# SparkFun_GPS_ZED-F9R_BoB.net
KiCad netlist of a schematic drawn in EAGLE
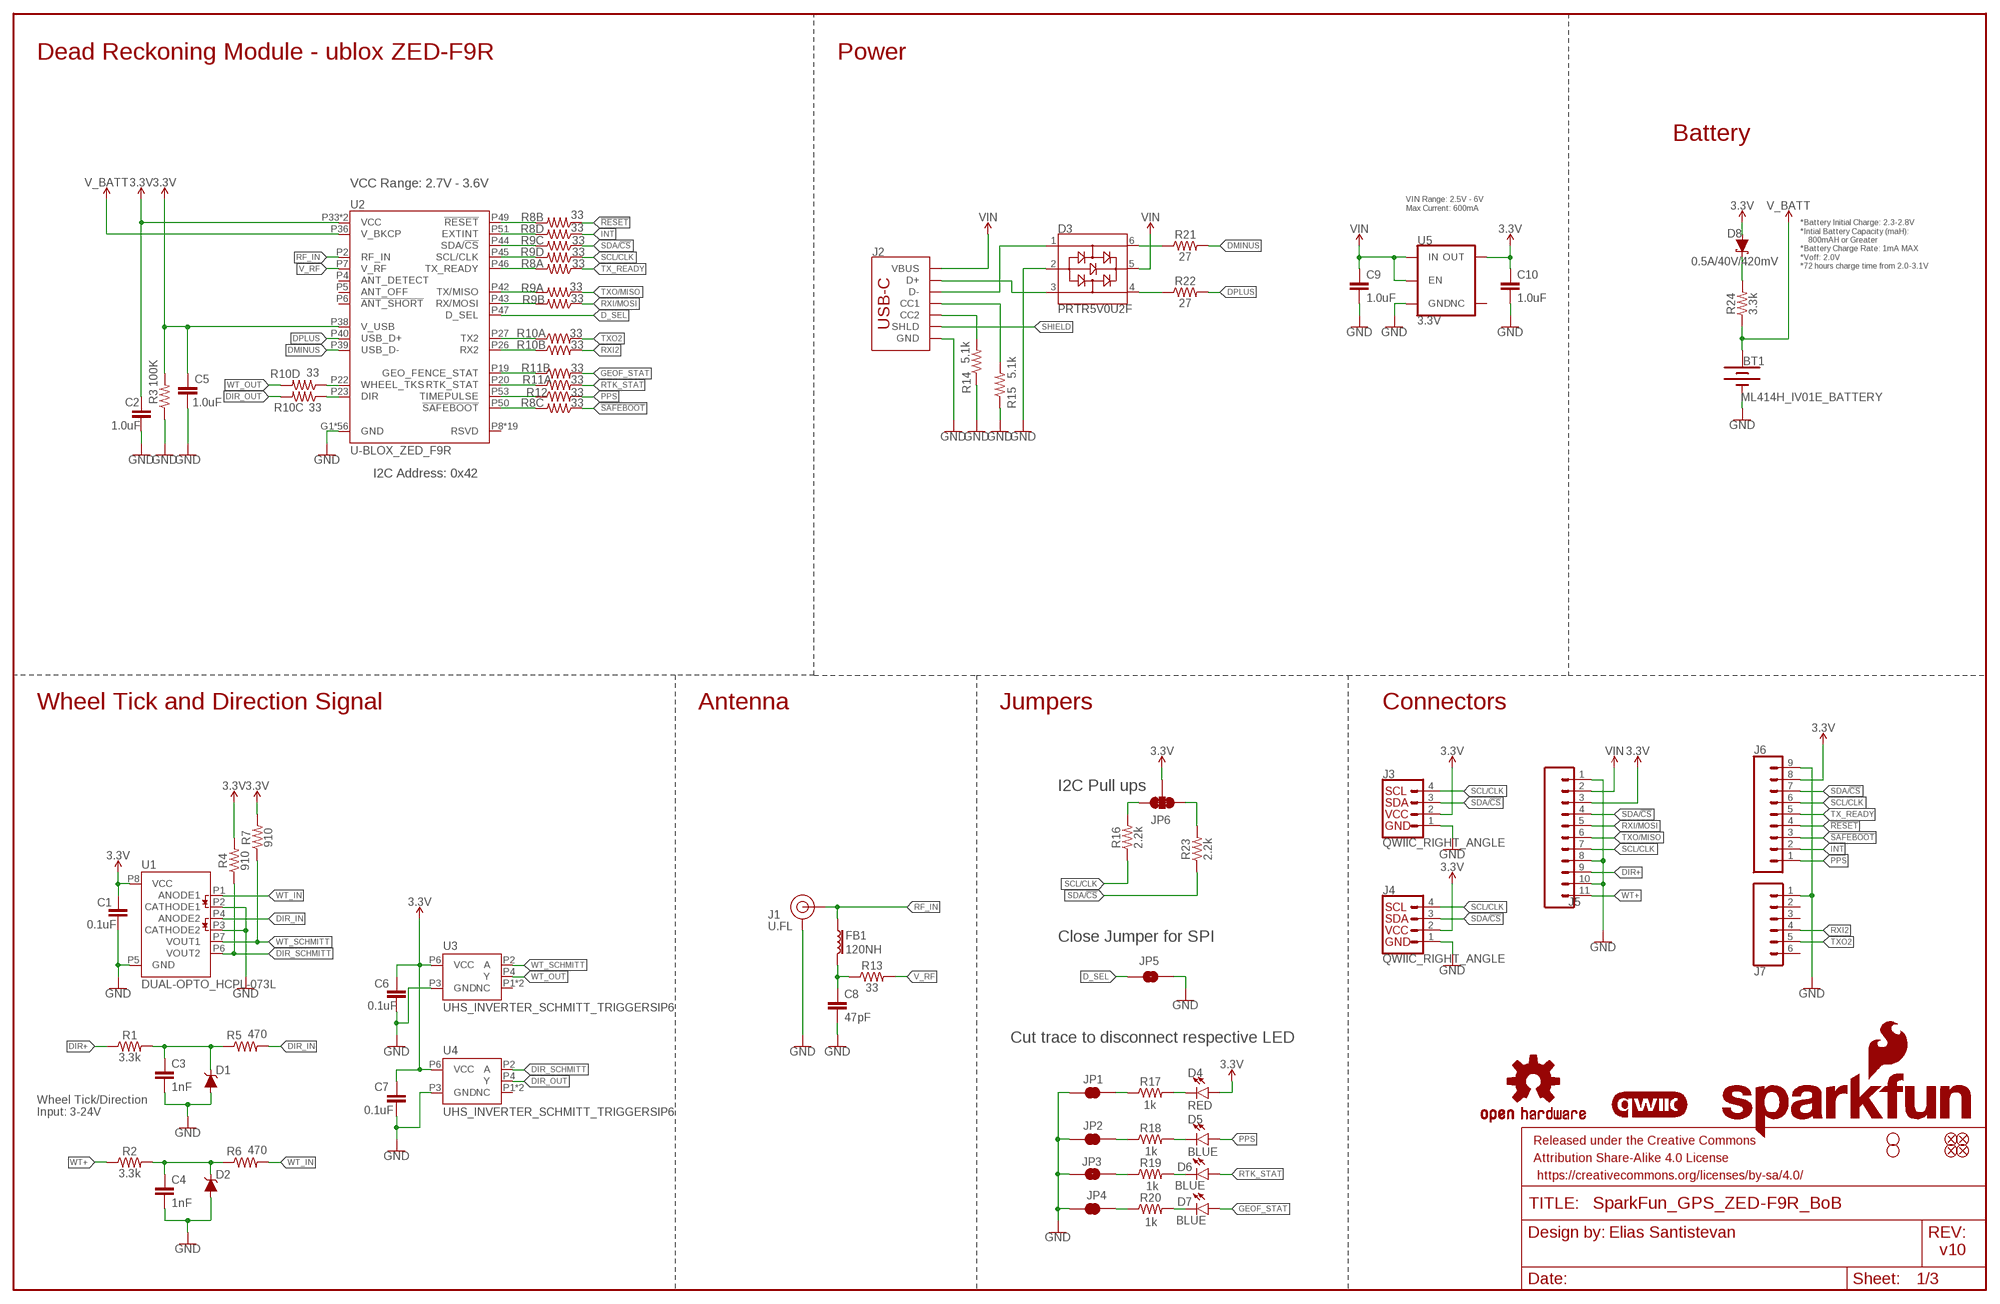
[diagram p0: schematic, sheet 1]

(export (version "E")
  (design (tool "Eeschema 10.0.6"))
  (components
    (comp (ref "$1_25_$_2020-03-30_22-52-05")
      (value "STAND-OFFTIGHT")
      (footprint "eagle-import:STAND-OFF-TIGHT")
      (libsource (lib "eagle-import") (part "STAND-OFFTIGHT"))
    )
    (comp (ref "BT1")
      (value "ML414H_IV01E_BATTERY")
      (footprint "eagle-import:ML414H_IV01E")
      (libsource (lib "eagle-import") (part "ML414H_IV01E_BATTERY"))
    )
    (comp (ref "C1")
      (value "0.1uF")
      (footprint "eagle-import:0402")
      (libsource (lib "eagle-import") (part "0.1UF-0402-10V-10%-X7R"))
    )
    (comp (ref "C2")
      (value "1.0uF")
      (footprint "eagle-import:0603")
      (libsource (lib "eagle-import") (part "1.0UF-0603-16V-10%-X7R"))
    )
    (comp (ref "C3")
      (value "1nF")
      (footprint "eagle-import:0402")
      (libsource (lib "eagle-import") (part "1.0NF/1000PF-0402-25V-10%-X7R"))
    )
    (comp (ref "C4")
      (value "1nF")
      (footprint "eagle-import:0402")
      (libsource (lib "eagle-import") (part "1.0NF/1000PF-0402-25V-10%-X7R"))
    )
    (comp (ref "C5")
      (value "1.0uF")
      (footprint "eagle-import:0603")
      (libsource (lib "eagle-import") (part "1.0UF-0603-16V-10%-X7R"))
    )
    (comp (ref "C6")
      (value "0.1uF")
      (footprint "eagle-import:0402")
      (libsource (lib "eagle-import") (part "0.1UF-0402-10V-10%-X7R"))
    )
    (comp (ref "C7")
      (value "0.1uF")
      (footprint "eagle-import:0402")
      (libsource (lib "eagle-import") (part "0.1UF-0402-10V-10%-X7R"))
    )
    (comp (ref "C8")
      (value "47pF")
      (footprint "eagle-import:0402")
      (libsource (lib "eagle-import") (part "47PF-0402-25V-5%-X7R"))
    )
    (comp (ref "C9")
      (value "1.0uF")
      (footprint "eagle-import:0603")
      (libsource (lib "eagle-import") (part "1.0UF-0603-16V-10%-X7R"))
    )
    (comp (ref "C10")
      (value "1.0uF")
      (footprint "eagle-import:0603")
      (libsource (lib "eagle-import") (part "1.0UF-0603-16V-10%-X7R"))
    )
    (comp (ref "D1")
      (value "15V")
      (footprint "eagle-import:SOT23-3")
      (libsource (lib "eagle-import") (part "DIODE-ZENER-BZX84C15LT3G"))
    )
    (comp (ref "D2")
      (value "15V")
      (footprint "eagle-import:SOT23-3")
      (libsource (lib "eagle-import") (part "DIODE-ZENER-BZX84C15LT3G"))
    )
    (comp (ref "D3")
      (value "PRTR5V0U2F")
      (footprint "eagle-import:SOT886")
      (libsource (lib "eagle-import") (part "PRTR5V0U2F"))
    )
    (comp (ref "D4")
      (value "RED")
      (footprint "eagle-import:LED-0603")
      (libsource (lib "eagle-import") (part "LED-RED0603"))
    )
    (comp (ref "D5")
      (value "BLUE")
      (footprint "eagle-import:LED-0603")
      (libsource (lib "eagle-import") (part "LED-BLUE0603"))
    )
    (comp (ref "D6")
      (value "BLUE")
      (footprint "eagle-import:LED-0603")
      (libsource (lib "eagle-import") (part "LED-BLUE0603"))
    )
    (comp (ref "D7")
      (value "BLUE")
      (footprint "eagle-import:LED-0603")
      (libsource (lib "eagle-import") (part "LED-BLUE0603"))
    )
    (comp (ref "D8")
      (value "0.5A/40V/420mV")
      (footprint "eagle-import:SOD-323")
      (libsource (lib "eagle-import") (part "DIODE-SCHOTTKY-PMEG4005EJ"))
    )
    (comp (ref "FB1")
      (value "120NH")
      (footprint "eagle-import:0402_MURATA")
      (libsource (lib "eagle-import") (part "FERRITE_BEAD_GNSS"))
    )
    (comp (ref "FD1")
      (value "FIDUCIALUFIDUCIAL")
      (footprint "eagle-import:FIDUCIAL-MICRO")
      (libsource (lib "eagle-import") (part "FIDUCIALUFIDUCIAL"))
    )
    (comp (ref "FD2")
      (value "FIDUCIALUFIDUCIAL")
      (footprint "eagle-import:FIDUCIAL-MICRO")
      (libsource (lib "eagle-import") (part "FIDUCIALUFIDUCIAL"))
    )
    (comp (ref "FD3")
      (value "FIDUCIALUFIDUCIAL")
      (footprint "eagle-import:FIDUCIAL-MICRO")
      (libsource (lib "eagle-import") (part "FIDUCIALUFIDUCIAL"))
    )
    (comp (ref "FD4")
      (value "FIDUCIALUFIDUCIAL")
      (footprint "eagle-import:FIDUCIAL-MICRO")
      (libsource (lib "eagle-import") (part "FIDUCIALUFIDUCIAL"))
    )
    (comp (ref "FRAME1")
      (value "FRAME-LEDGER")
      (footprint "eagle-import:CREATIVE_COMMONS")
      (libsource (lib "eagle-import") (part "FRAME-LEDGER"))
    )
    (comp (ref "H2")
      (value "STAND-OFFTIGHT")
      (footprint "eagle-import:STAND-OFF-TIGHT")
      (libsource (lib "eagle-import") (part "STAND-OFFTIGHT"))
    )
    (comp (ref "J1")
      (value "U.FL")
      (footprint "eagle-import:U.FL")
      (libsource (lib "eagle-import") (part "U.FL2PIN"))
    )
    (comp (ref "J2")
      (value "USB_C_2-LAYER_PADS")
      (footprint "eagle-import:USB-C-16P-2LAYER-PADS")
      (libsource (lib "eagle-import") (part "USB_C_2-LAYER_PADS"))
    )
    (comp (ref "J3")
      (value "QWIIC_RIGHT_ANGLE")
      (footprint "eagle-import:JST04_1MM_RA")
      (libsource (lib "eagle-import") (part "QWIIC_CONNECTORJS-1MM"))
    )
    (comp (ref "J4")
      (value "QWIIC_RIGHT_ANGLE")
      (footprint "eagle-import:JST04_1MM_RA")
      (libsource (lib "eagle-import") (part "QWIIC_CONNECTORJS-1MM"))
    )
    (comp (ref "J5")
      (value "CONN_111X11_NO_SILK")
      (footprint "eagle-import:1X11_NO_SILK")
      (libsource (lib "eagle-import") (part "CONN_111X11_NO_SILK"))
    )
    (comp (ref "J6")
      (value "CONN_09NO_SILK")
      (footprint "eagle-import:1X09_NO_SILK")
      (libsource (lib "eagle-import") (part "CONN_09NO_SILK"))
    )
    (comp (ref "J7")
      (value "CONN_06NO_SILK_NO_POP")
      (footprint "eagle-import:1X06_NO_SILK")
      (libsource (lib "eagle-import") (part "CONN_06NO_SILK_NO_POP"))
    )
    (comp (ref "JP1")
      (value "JUMPER-SMT_2_NC_TRACE_SILK")
      (footprint "eagle-import:SMT-JUMPER_2_NC_TRACE_SILK")
      (libsource (lib "eagle-import") (part "JUMPER-SMT_2_NC_TRACE_SILK"))
    )
    (comp (ref "JP2")
      (value "JUMPER-SMT_2_NC_TRACE_SILK")
      (footprint "eagle-import:SMT-JUMPER_2_NC_TRACE_SILK")
      (libsource (lib "eagle-import") (part "JUMPER-SMT_2_NC_TRACE_SILK"))
    )
    (comp (ref "JP3")
      (value "JUMPER-SMT_2_NC_TRACE_SILK")
      (footprint "eagle-import:SMT-JUMPER_2_NC_TRACE_SILK")
      (libsource (lib "eagle-import") (part "JUMPER-SMT_2_NC_TRACE_SILK"))
    )
    (comp (ref "JP4")
      (value "JUMPER-SMT_2_NC_TRACE_SILK")
      (footprint "eagle-import:SMT-JUMPER_2_NC_TRACE_SILK")
      (libsource (lib "eagle-import") (part "JUMPER-SMT_2_NC_TRACE_SILK"))
    )
    (comp (ref "JP5")
      (value "JUMPER-SMT_2_NO_SILK")
      (footprint "eagle-import:SMT-JUMPER_2_NO_SILK")
      (libsource (lib "eagle-import") (part "JUMPER-SMT_2_NO_SILK"))
    )
    (comp (ref "JP6")
      (value "JUMPER-SMT_3_2-NC_TRACE_SILK")
      (footprint "eagle-import:SMT-JUMPER_3_2-NC_TRACE_SILK")
      (libsource (lib "eagle-import") (part "JUMPER-SMT_3_2-NC_TRACE_SILK"))
    )
    (comp (ref "LOGO1")
      (value "OSHW-LOGOM")
      (footprint "eagle-import:OSHW-LOGO-M")
      (libsource (lib "eagle-import") (part "OSHW-LOGOM"))
    )
    (comp (ref "LOGO2")
      (value "QWIIC_LOGO_4MM")
      (footprint "eagle-import:QWIIC_4MM")
      (libsource (lib "eagle-import") (part "QWIIC_LOGO_4MM"))
    )
    (comp (ref "LOGO3")
      (value "SFE_LOGO_NAME_FLAME.2_INCH")
      (footprint "eagle-import:SFE_LOGO_NAME_FLAME_.2")
      (libsource (lib "eagle-import") (part "SFE_LOGO_NAME_FLAME.2_INCH"))
    )
    (comp (ref "R1")
      (value "3.3k")
      (footprint "eagle-import:0603")
      (libsource (lib "eagle-import") (part "3.3KOHM-0603-1/10W-1%"))
    )
    (comp (ref "R2")
      (value "3.3k")
      (footprint "eagle-import:0603")
      (libsource (lib "eagle-import") (part "3.3KOHM-0603-1/10W-1%"))
    )
    (comp (ref "R3")
      (value "100K")
      (footprint "eagle-import:0402")
      (libsource (lib "eagle-import") (part "100KOHM-0402-1/16W-1%"))
    )
    (comp (ref "R4")
      (value "910")
      (footprint "eagle-import:0603")
      (libsource (lib "eagle-import") (part "910OHM-0603-1/10W-5%"))
    )
    (comp (ref "R5")
      (value "470")
      (footprint "eagle-import:0603")
      (libsource (lib "eagle-import") (part "470OHM-0603-1/10W-1%"))
    )
    (comp (ref "R6")
      (value "470")
      (footprint "eagle-import:0603")
      (libsource (lib "eagle-import") (part "470OHM-0603-1/10W-1%"))
    )
    (comp (ref "R7")
      (value "910")
      (footprint "eagle-import:0603")
      (libsource (lib "eagle-import") (part "910OHM-0603-1/10W-5%"))
    )
    (comp (ref "R8")
      (value "33")
      (footprint "eagle-import:1206_RA")
      (libsource (lib "eagle-import") (part "33OHM_RA-1206-1/16W-5%"))
    )
    (comp (ref "R9")
      (value "33")
      (footprint "eagle-import:1206_RA")
      (libsource (lib "eagle-import") (part "33OHM_RA-1206-1/16W-5%"))
    )
    (comp (ref "R10")
      (value "33")
      (footprint "eagle-import:1206_RA")
      (libsource (lib "eagle-import") (part "33OHM_RA-1206-1/16W-5%"))
    )
    (comp (ref "R11")
      (value "33")
      (footprint "eagle-import:1206_RA")
      (libsource (lib "eagle-import") (part "33OHM_RA-1206-1/16W-5%"))
    )
    (comp (ref "R12")
      (value "33")
      (footprint "eagle-import:0603")
      (libsource (lib "eagle-import") (part "33OHM-0603-1/10W-1%"))
    )
    (comp (ref "R13")
      (value "33")
      (footprint "eagle-import:0603")
      (libsource (lib "eagle-import") (part "33OHM-0603-1/10W-1%"))
    )
    (comp (ref "R14")
      (value "5.1k")
      (footprint "eagle-import:0402")
      (libsource (lib "eagle-import") (part "5.1KOHM-0402-1/16W-1%"))
    )
    (comp (ref "R15")
      (value "5.1k")
      (footprint "eagle-import:0402")
      (libsource (lib "eagle-import") (part "5.1KOHM-0402-1/16W-1%"))
    )
    (comp (ref "R16")
      (value "2.2k")
      (footprint "eagle-import:0603")
      (libsource (lib "eagle-import") (part "2.2KOHM-0603-1/10W-1%"))
    )
    (comp (ref "R17")
      (value "1KOHM-0402-1/16W-1%")
      (footprint "eagle-import:0402")
      (libsource (lib "eagle-import") (part "1KOHM-0402-1/16W-1%"))
    )
    (comp (ref "R18")
      (value "1KOHM-0402-1/16W-1%")
      (footprint "eagle-import:0402")
      (libsource (lib "eagle-import") (part "1KOHM-0402-1/16W-1%"))
    )
    (comp (ref "R19")
      (value "1KOHM-0402-1/16W-1%")
      (footprint "eagle-import:0402")
      (libsource (lib "eagle-import") (part "1KOHM-0402-1/16W-1%"))
    )
    (comp (ref "R20")
      (value "1KOHM-0402-1/16W-1%")
      (footprint "eagle-import:0402")
      (libsource (lib "eagle-import") (part "1KOHM-0402-1/16W-1%"))
    )
    (comp (ref "R21")
      (value "27")
      (footprint "eagle-import:0603")
      (libsource (lib "eagle-import") (part "27OHM-0603-1/10W-1%"))
    )
    (comp (ref "R22")
      (value "27")
      (footprint "eagle-import:0603")
      (libsource (lib "eagle-import") (part "27OHM-0603-1/10W-1%"))
    )
    (comp (ref "R23")
      (value "2.2k")
      (footprint "eagle-import:0603")
      (libsource (lib "eagle-import") (part "2.2KOHM-0603-1/10W-1%"))
    )
    (comp (ref "R24")
      (value "3.3k")
      (footprint "eagle-import:0603")
      (libsource (lib "eagle-import") (part "3.3KOHM-0603-1/10W-1%"))
    )
    (comp (ref "U1")
      (value "DUAL-OPTO_HCPL-073L")
      (footprint "eagle-import:SOP_8-PIN")
      (libsource (lib "eagle-import") (part "DUAL-OPTO_HCPL-073L"))
    )
    (comp (ref "U2")
      (value "U-BLOX_ZED_F9R")
      (footprint "eagle-import:UBLOX_ZED_F9R")
      (libsource (lib "eagle-import") (part "U-BLOX_ZED_F9R"))
    )
    (comp (ref "U3")
      (value "UHS_INVERTER_SCHMITT_TRIGGERSIP6")
      (footprint "eagle-import:SIP6")
      (libsource (lib "eagle-import") (part "UHS_INVERTER_SCHMITT_TRIGGERSIP6"))
    )
    (comp (ref "U4")
      (value "UHS_INVERTER_SCHMITT_TRIGGERSIP6")
      (footprint "eagle-import:SIP6")
      (libsource (lib "eagle-import") (part "UHS_INVERTER_SCHMITT_TRIGGERSIP6"))
    )
    (comp (ref "U5")
      (value "3.3V")
      (footprint "eagle-import:SOT23-5")
      (libsource (lib "eagle-import") (part "V_REG_AP2112K-3.3V"))
    )
  )
  (nets
    (net (code "1") (name "3.3V") (class "Default")
      (node (ref "C1") (pin "1") (pinfunction "1_1") (pintype "passive"))
      (node (ref "C10") (pin "1") (pinfunction "1_1") (pintype "passive"))
      (node (ref "C2") (pin "1") (pinfunction "1_1") (pintype "passive"))
      (node (ref "C5") (pin "1") (pinfunction "1_1") (pintype "passive"))
      (node (ref "C6") (pin "1") (pinfunction "1_1") (pintype "passive"))
      (node (ref "C7") (pin "1") (pinfunction "1_1") (pintype "passive"))
      (node (ref "D4") (pin "A") (pinfunction "A_A") (pintype "passive"))
      (node (ref "D8") (pin "A") (pinfunction "A_A") (pintype "passive"))
      (node (ref "J3") (pin "2") (pinfunction "2_2") (pintype "power_in"))
      (node (ref "J4") (pin "2") (pinfunction "2_2") (pintype "power_in"))
      (node (ref "J5") (pin "3") (pinfunction "3_3") (pintype "passive"))
      (node (ref "J6") (pin "8") (pinfunction "8_8") (pintype "passive"))
      (node (ref "JP6") (pin "2") (pinfunction "2_2") (pintype "passive"))
      (node (ref "R3") (pin "2") (pinfunction "2_2") (pintype "passive"))
      (node (ref "R4") (pin "2") (pinfunction "2_2") (pintype "passive"))
      (node (ref "R7") (pin "2") (pinfunction "2_2") (pintype "passive"))
      (node (ref "U1") (pin "P8") (pinfunction "VCC_P8") (pintype "power_in"))
      (node (ref "U2") (pin "P33") (pinfunction "VCC_P33") (pintype "power_in"))
      (node (ref "U2") (pin "P34") (pinfunction "VCC_P34") (pintype "power_in"))
      (node (ref "U2") (pin "P38") (pinfunction "V_USB_P38") (pintype "power_in"))
      (node (ref "U3") (pin "P6") (pinfunction "VCC_P6") (pintype "power_in"))
      (node (ref "U4") (pin "P6") (pinfunction "VCC_P6") (pintype "power_in"))
      (node (ref "U5") (pin "5") (pinfunction "OUT_5") (pintype "passive"))
    )
    (net (code "2") (name "DIR+") (class "Default")
      (node (ref "J5") (pin "9") (pinfunction "9_9") (pintype "passive"))
      (node (ref "R1") (pin "1") (pinfunction "1_1") (pintype "passive"))
    )
    (net (code "3") (name "DIR_IN") (class "Default")
      (node (ref "R5") (pin "2") (pinfunction "2_2") (pintype "passive"))
      (node (ref "U1") (pin "P4") (pinfunction "ANODE2_P4") (pintype "input"))
    )
    (net (code "4") (name "DIR_OUT") (class "Default")
      (node (ref "R10") (pin "P6") (pinfunction "2_P6") (pintype "passive"))
      (node (ref "U4") (pin "P4") (pinfunction "Y_P4") (pintype "bidirectional"))
    )
    (net (code "5") (name "DIR_SCHMITT") (class "Default")
      (node (ref "R4") (pin "1") (pinfunction "1_1") (pintype "passive"))
      (node (ref "U1") (pin "P6") (pinfunction "VOUT2_P6") (pintype "output"))
      (node (ref "U4") (pin "P2") (pinfunction "A_P2") (pintype "bidirectional"))
    )
    (net (code "6") (name "DMINUS") (class "Default")
      (node (ref "R21") (pin "2") (pinfunction "2_2") (pintype "passive"))
      (node (ref "U2") (pin "P39") (pinfunction "USB_D-_P39") (pintype "bidirectional"))
    )
    (net (code "7") (name "DPLUS") (class "Default")
      (node (ref "R22") (pin "2") (pinfunction "2_2") (pintype "passive"))
      (node (ref "U2") (pin "P40") (pinfunction "USB_D+_P40") (pintype "bidirectional"))
    )
    (net (code "8") (name "D_SEL") (class "Default")
      (node (ref "JP5") (pin "1") (pinfunction "1_1") (pintype "passive"))
      (node (ref "U2") (pin "P47") (pinfunction "D_SEL_P47") (pintype "bidirectional"))
    )
    (net (code "9") (name "GEOF_STAT") (class "Default")
      (node (ref "D7") (pin "A") (pinfunction "A_A") (pintype "passive"))
      (node (ref "R11") (pin "P7") (pinfunction "2_P7") (pintype "passive"))
    )
    (net (code "10") (name "GND") (class "Default")
      (node (ref "BT1") (pin "-") (pinfunction "-_-") (pintype "power_in"))
      (node (ref "C1") (pin "2") (pinfunction "2_2") (pintype "passive"))
      (node (ref "C10") (pin "2") (pinfunction "2_2") (pintype "passive"))
      (node (ref "C2") (pin "2") (pinfunction "2_2") (pintype "passive"))
      (node (ref "C3") (pin "2") (pinfunction "2_2") (pintype "passive"))
      (node (ref "C4") (pin "2") (pinfunction "2_2") (pintype "passive"))
      (node (ref "C5") (pin "2") (pinfunction "2_2") (pintype "passive"))
      (node (ref "C6") (pin "2") (pinfunction "2_2") (pintype "passive"))
      (node (ref "C7") (pin "2") (pinfunction "2_2") (pintype "passive"))
      (node (ref "C8") (pin "2") (pinfunction "2_2") (pintype "passive"))
      (node (ref "C9") (pin "2") (pinfunction "2_2") (pintype "passive"))
      (node (ref "D1") (pin "1") (pinfunction "A_1") (pintype "passive"))
      (node (ref "D2") (pin "1") (pinfunction "A_1") (pintype "passive"))
      (node (ref "D3") (pin "2") (pinfunction "2_2") (pintype "bidirectional"))
      (node (ref "J1") (pin "1") (pinfunction "GND_1") (pintype "bidirectional"))
      (node (ref "J1") (pin "2") (pinfunction "GND_2") (pintype "bidirectional"))
      (node (ref "J2") (pin "GND") (pinfunction "GND_GND") (pintype "bidirectional"))
      (node (ref "J2") (pin "GND2") (pinfunction "GND_GND2") (pintype "bidirectional"))
      (node (ref "J3") (pin "1") (pinfunction "1_1") (pintype "power_in"))
      (node (ref "J4") (pin "1") (pinfunction "1_1") (pintype "power_in"))
      (node (ref "J5") (pin "1") (pinfunction "1_1") (pintype "passive"))
      (node (ref "J5") (pin "10") (pinfunction "10_10") (pintype "passive"))
      (node (ref "J5") (pin "8") (pinfunction "8_8") (pintype "passive"))
      (node (ref "J6") (pin "9") (pinfunction "9_9") (pintype "passive"))
      (node (ref "J7") (pin "1") (pinfunction "1_1") (pintype "passive"))
      (node (ref "JP1") (pin "1") (pinfunction "1_1") (pintype "passive"))
      (node (ref "JP2") (pin "1") (pinfunction "1_1") (pintype "passive"))
      (node (ref "JP3") (pin "1") (pinfunction "1_1") (pintype "passive"))
      (node (ref "JP4") (pin "1") (pinfunction "1_1") (pintype "passive"))
      (node (ref "JP5") (pin "2") (pinfunction "2_2") (pintype "passive"))
      (node (ref "R14") (pin "1") (pinfunction "1_1") (pintype "passive"))
      (node (ref "R15") (pin "1") (pinfunction "1_1") (pintype "passive"))
      (node (ref "R3") (pin "1") (pinfunction "1_1") (pintype "passive"))
      (node (ref "U1") (pin "P2") (pinfunction "CATHODE1_P2") (pintype "input"))
      (node (ref "U1") (pin "P3") (pinfunction "CATHODE2_P3") (pintype "input"))
      (node (ref "U1") (pin "P5") (pinfunction "GND_P5") (pintype "power_in"))
      (node (ref "U2") (pin "G1") (pinfunction "GND_G1") (pintype "power_in"))
      (node (ref "U2") (pin "G10") (pinfunction "GND_G10") (pintype "power_in"))
      (node (ref "U2") (pin "G11") (pinfunction "GND_G11") (pintype "power_in"))
      (node (ref "U2") (pin "G12") (pinfunction "GND_G12") (pintype "power_in"))
      (node (ref "U2") (pin "G13") (pinfunction "GND_G13") (pintype "power_in"))
      (node (ref "U2") (pin "G14") (pinfunction "GND_G14") (pintype "power_in"))
      (node (ref "U2") (pin "G15") (pinfunction "GND_G15") (pintype "power_in"))
      (node (ref "U2") (pin "G16") (pinfunction "GND_G16") (pintype "power_in"))
      (node (ref "U2") (pin "G17") (pinfunction "GND_G17") (pintype "power_in"))
      (node (ref "U2") (pin "G18") (pinfunction "GND_G18") (pintype "power_in"))
      (node (ref "U2") (pin "G19") (pinfunction "GND_G19") (pintype "power_in"))
      (node (ref "U2") (pin "G2") (pinfunction "GND_G2") (pintype "power_in"))
      (node (ref "U2") (pin "G20") (pinfunction "GND_G20") (pintype "power_in"))
      (node (ref "U2") (pin "G21") (pinfunction "GND_G21") (pintype "power_in"))
      (node (ref "U2") (pin "G22") (pinfunction "GND_G22") (pintype "power_in"))
      (node (ref "U2") (pin "G23") (pinfunction "GND_G23") (pintype "power_in"))
      (node (ref "U2") (pin "G24") (pinfunction "GND_G24") (pintype "power_in"))
      (node (ref "U2") (pin "G25") (pinfunction "GND_G25") (pintype "power_in"))
      (node (ref "U2") (pin "G26") (pinfunction "GND_G26") (pintype "power_in"))
      (node (ref "U2") (pin "G27") (pinfunction "GND_G27") (pintype "power_in"))
      (node (ref "U2") (pin "G28") (pinfunction "GND_G28") (pintype "power_in"))
      (node (ref "U2") (pin "G29") (pinfunction "GND_G29") (pintype "power_in"))
      (node (ref "U2") (pin "G3") (pinfunction "GND_G3") (pintype "power_in"))
      (node (ref "U2") (pin "G30") (pinfunction "GND_G30") (pintype "power_in"))
      (node (ref "U2") (pin "G31") (pinfunction "GND_G31") (pintype "power_in"))
      (node (ref "U2") (pin "G32") (pinfunction "GND_G32") (pintype "power_in"))
      (node (ref "U2") (pin "G33") (pinfunction "GND_G33") (pintype "power_in"))
      (node (ref "U2") (pin "G34") (pinfunction "GND_G34") (pintype "power_in"))
      (node (ref "U2") (pin "G35") (pinfunction "GND_G35") (pintype "power_in"))
      (node (ref "U2") (pin "G36") (pinfunction "GND_G36") (pintype "power_in"))
      (node (ref "U2") (pin "G37") (pinfunction "GND_G37") (pintype "power_in"))
      (node (ref "U2") (pin "G38") (pinfunction "GND_G38") (pintype "power_in"))
      (node (ref "U2") (pin "G39") (pinfunction "GND_G39") (pintype "power_in"))
      (node (ref "U2") (pin "G4") (pinfunction "GND_G4") (pintype "power_in"))
      (node (ref "U2") (pin "G40") (pinfunction "GND_G40") (pintype "power_in"))
      (node (ref "U2") (pin "G41") (pinfunction "GND_G41") (pintype "power_in"))
      (node (ref "U2") (pin "G42") (pinfunction "GND_G42") (pintype "power_in"))
      (node (ref "U2") (pin "G43") (pinfunction "GND_G43") (pintype "power_in"))
      (node (ref "U2") (pin "G44") (pinfunction "GND_G44") (pintype "power_in"))
      (node (ref "U2") (pin "G45") (pinfunction "GND_G45") (pintype "power_in"))
      (node (ref "U2") (pin "G46") (pinfunction "GND_G46") (pintype "power_in"))
      (node (ref "U2") (pin "G47") (pinfunction "GND_G47") (pintype "power_in"))
      (node (ref "U2") (pin "G48") (pinfunction "GND_G48") (pintype "power_in"))
      (node (ref "U2") (pin "G5") (pinfunction "GND_G5") (pintype "power_in"))
      (node (ref "U2") (pin "G6") (pinfunction "GND_G6") (pintype "power_in"))
      (node (ref "U2") (pin "G7") (pinfunction "GND_G7") (pintype "power_in"))
      (node (ref "U2") (pin "G8") (pinfunction "GND_G8") (pintype "power_in"))
      (node (ref "U2") (pin "G9") (pinfunction "GND_G9") (pintype "power_in"))
      (node (ref "U2") (pin "P1") (pinfunction "GND_P1") (pintype "power_in"))
      (node (ref "U2") (pin "P12") (pinfunction "GND_P12") (pintype "power_in"))
      (node (ref "U2") (pin "P14") (pinfunction "GND_P14") (pintype "power_in"))
      (node (ref "U2") (pin "P3") (pinfunction "GND_P3") (pintype "power_in"))
      (node (ref "U2") (pin "P32") (pinfunction "GND_P32") (pintype "power_in"))
      (node (ref "U2") (pin "P37") (pinfunction "GND_P37") (pintype "power_in"))
      (node (ref "U2") (pin "P41") (pinfunction "GND_P41") (pintype "power_in"))
      (node (ref "U2") (pin "P48") (pinfunction "GND_P48") (pintype "power_in"))
      (node (ref "U3") (pin "P3") (pinfunction "GND_P3") (pintype "power_in"))
      (node (ref "U4") (pin "P3") (pinfunction "GND_P3") (pintype "power_in"))
      (node (ref "U5") (pin "2") (pinfunction "GND_2") (pintype "input"))
    )
    (net (code "11") (name "INT") (class "Default")
      (node (ref "J6") (pin "2") (pinfunction "2_2") (pintype "passive"))
      (node (ref "R8") (pin "P4") (pinfunction "1_P4") (pintype "passive"))
    )
    (net (code "12") (name "Net-(D1-C)") (class "Default")
      (node (ref "C3") (pin "1") (pinfunction "1_1") (pintype "passive"))
      (node (ref "D1") (pin "3") (pinfunction "C_3") (pintype "passive"))
      (node (ref "R1") (pin "2") (pinfunction "2_2") (pintype "passive"))
      (node (ref "R5") (pin "1") (pinfunction "1_1") (pintype "passive"))
    )
    (net (code "13") (name "Net-(D2-C)") (class "Default")
      (node (ref "C4") (pin "1") (pinfunction "1_1") (pintype "passive"))
      (node (ref "D2") (pin "3") (pinfunction "C_3") (pintype "passive"))
      (node (ref "R2") (pin "2") (pinfunction "2_2") (pintype "passive"))
      (node (ref "R6") (pin "1") (pinfunction "1_1") (pintype "passive"))
    )
    (net (code "14") (name "Net-(D3-Pad1)") (class "Default")
      (node (ref "D3") (pin "1") (pinfunction "1_1") (pintype "bidirectional"))
      (node (ref "J2") (pin "A7") (pinfunction "D-_A7") (pintype "bidirectional"))
      (node (ref "J2") (pin "B7") (pinfunction "D-_B7") (pintype "bidirectional"))
    )
    (net (code "15") (name "Net-(D3-Pad3)") (class "Default")
      (node (ref "D3") (pin "3") (pinfunction "3_3") (pintype "bidirectional"))
      (node (ref "J2") (pin "A6") (pinfunction "D+_A6") (pintype "bidirectional"))
      (node (ref "J2") (pin "B6") (pinfunction "D+_B6") (pintype "bidirectional"))
    )
    (net (code "16") (name "Net-(D3-Pad4)") (class "Default")
      (node (ref "D3") (pin "4") (pinfunction "4_4") (pintype "bidirectional"))
      (node (ref "R22") (pin "1") (pinfunction "1_1") (pintype "passive"))
    )
    (net (code "17") (name "Net-(D3-Pad6)") (class "Default")
      (node (ref "D3") (pin "6") (pinfunction "6_6") (pintype "bidirectional"))
      (node (ref "R21") (pin "1") (pinfunction "1_1") (pintype "passive"))
    )
    (net (code "18") (name "Net-(D4-PadC)") (class "Default")
      (node (ref "D4") (pin "C") (pinfunction "C_C") (pintype "passive"))
      (node (ref "R17") (pin "2") (pinfunction "2_2") (pintype "passive"))
    )
    (net (code "19") (name "Net-(D5-PadC)") (class "Default")
      (node (ref "D5") (pin "C") (pinfunction "C_C") (pintype "passive"))
      (node (ref "R18") (pin "2") (pinfunction "2_2") (pintype "passive"))
    )
    (net (code "20") (name "Net-(D6-PadC)") (class "Default")
      (node (ref "D6") (pin "C") (pinfunction "C_C") (pintype "passive"))
      (node (ref "R19") (pin "2") (pinfunction "2_2") (pintype "passive"))
    )
    (net (code "21") (name "Net-(D7-PadC)") (class "Default")
      (node (ref "D7") (pin "C") (pinfunction "C_C") (pintype "passive"))
      (node (ref "R20") (pin "2") (pinfunction "2_2") (pintype "passive"))
    )
    (net (code "22") (name "Net-(D8-PadC)") (class "Default")
      (node (ref "D8") (pin "C") (pinfunction "C_C") (pintype "passive"))
      (node (ref "R24") (pin "2") (pinfunction "2_2") (pintype "passive"))
    )
    (net (code "23") (name "Net-(FB1-2)") (class "Default")
      (node (ref "C8") (pin "1") (pinfunction "1_1") (pintype "passive"))
      (node (ref "FB1") (pin "P2") (pinfunction "2_P2") (pintype "passive"))
      (node (ref "R13") (pin "1") (pinfunction "1_1") (pintype "passive"))
    )
    (net (code "24") (name "Net-(J2-CC1)") (class "Default")
      (node (ref "J2") (pin "A5") (pinfunction "CC1_A5") (pintype "bidirectional"))
      (node (ref "R15") (pin "2") (pinfunction "2_2") (pintype "passive"))
    )
    (net (code "25") (name "Net-(J2-CC2)") (class "Default")
      (node (ref "J2") (pin "B5") (pinfunction "CC2_B5") (pintype "bidirectional"))
      (node (ref "R14") (pin "2") (pinfunction "2_2") (pintype "passive"))
    )
    (net (code "26") (name "Net-(JP1-Pad2)") (class "Default")
      (node (ref "JP1") (pin "2") (pinfunction "2_2") (pintype "passive"))
      (node (ref "R17") (pin "1") (pinfunction "1_1") (pintype "passive"))
    )
    (net (code "27") (name "Net-(JP2-Pad2)") (class "Default")
      (node (ref "JP2") (pin "2") (pinfunction "2_2") (pintype "passive"))
      (node (ref "R18") (pin "1") (pinfunction "1_1") (pintype "passive"))
    )
    (net (code "28") (name "Net-(JP3-Pad2)") (class "Default")
      (node (ref "JP3") (pin "2") (pinfunction "2_2") (pintype "passive"))
      (node (ref "R19") (pin "1") (pinfunction "1_1") (pintype "passive"))
    )
    (net (code "29") (name "Net-(JP4-Pad2)") (class "Default")
      (node (ref "JP4") (pin "2") (pinfunction "2_2") (pintype "passive"))
      (node (ref "R20") (pin "1") (pinfunction "1_1") (pintype "passive"))
    )
    (net (code "30") (name "Net-(JP6-Pad1)") (class "Default")
      (node (ref "JP6") (pin "1") (pinfunction "1_1") (pintype "passive"))
      (node (ref "R23") (pin "2") (pinfunction "2_2") (pintype "passive"))
    )
    (net (code "31") (name "Net-(JP6-Pad3)") (class "Default")
      (node (ref "JP6") (pin "3") (pinfunction "3_3") (pintype "passive"))
      (node (ref "R16") (pin "2") (pinfunction "2_2") (pintype "passive"))
    )
    (net (code "32") (name "Net-(R8A-2)") (class "Default")
      (node (ref "R8") (pin "P8") (pinfunction "2_P8") (pintype "passive"))
      (node (ref "U2") (pin "P46") (pinfunction "TX_READY_P46") (pintype "bidirectional"))
    )
    (net (code "33") (name "Net-(R8B-2)") (class "Default")
      (node (ref "R8") (pin "P7") (pinfunction "2_P7") (pintype "passive"))
      (node (ref "U2") (pin "P49") (pinfunction "~{RESET}_P49") (pintype "bidirectional"))
    )
    (net (code "34") (name "Net-(R8C-2)") (class "Default")
      (node (ref "R8") (pin "P6") (pinfunction "2_P6") (pintype "passive"))
      (node (ref "U2") (pin "P50") (pinfunction "~{SAFEBOOT}_P50") (pintype "input"))
    )
    (net (code "35") (name "Net-(R8D-2)") (class "Default")
      (node (ref "R8") (pin "P5") (pinfunction "2_P5") (pintype "passive"))
      (node (ref "U2") (pin "P51") (pinfunction "EXTINT_P51") (pintype "bidirectional"))
    )
    (net (code "36") (name "Net-(R9A-2)") (class "Default")
      (node (ref "R9") (pin "P8") (pinfunction "2_P8") (pintype "passive"))
      (node (ref "U2") (pin "P42") (pinfunction "TX/MISO_P42") (pintype "bidirectional"))
    )
    (net (code "37") (name "Net-(R9B-2)") (class "Default")
      (node (ref "R9") (pin "P7") (pinfunction "2_P7") (pintype "passive"))
      (node (ref "U2") (pin "P43") (pinfunction "RX/MOSI_P43") (pintype "bidirectional"))
    )
    (net (code "38") (name "Net-(R9C-2)") (class "Default")
      (node (ref "R9") (pin "P6") (pinfunction "2_P6") (pintype "passive"))
      (node (ref "U2") (pin "P44") (pinfunction "SDA/~{CS}_P44") (pintype "bidirectional"))
    )
    (net (code "39") (name "Net-(R9D-2)") (class "Default")
      (node (ref "R9") (pin "P5") (pinfunction "2_P5") (pintype "passive"))
      (node (ref "U2") (pin "P45") (pinfunction "SCL/CLK_P45") (pintype "bidirectional"))
    )
    (net (code "40") (name "Net-(R10A-1)") (class "Default")
      (node (ref "R10") (pin "P1") (pinfunction "1_P1") (pintype "passive"))
      (node (ref "U2") (pin "P27") (pinfunction "TX2_P27") (pintype "output"))
    )
    (net (code "41") (name "Net-(R10B-1)") (class "Default")
      (node (ref "R10") (pin "P2") (pinfunction "1_P2") (pintype "passive"))
      (node (ref "U2") (pin "P26") (pinfunction "RX2_P26") (pintype "input"))
    )
    (net (code "42") (name "Net-(R10C-1)") (class "Default")
      (node (ref "R10") (pin "P3") (pinfunction "1_P3") (pintype "passive"))
      (node (ref "U2") (pin "P23") (pinfunction "DIR_P23") (pintype "input"))
    )
    (net (code "43") (name "Net-(R10D-1)") (class "Default")
      (node (ref "R10") (pin "P4") (pinfunction "1_P4") (pintype "passive"))
      (node (ref "U2") (pin "P22") (pinfunction "WHEEL_TKS_P22") (pintype "input"))
    )
    (net (code "44") (name "Net-(R11A-1)") (class "Default")
      (node (ref "R11") (pin "P1") (pinfunction "1_P1") (pintype "passive"))
      (node (ref "U2") (pin "P20") (pinfunction "RTK_STAT_P20") (pintype "output"))
    )
    (net (code "45") (name "Net-(R11B-1)") (class "Default")
      (node (ref "R11") (pin "P2") (pinfunction "1_P2") (pintype "passive"))
      (node (ref "U2") (pin "P19") (pinfunction "GEO_FENCE_STAT_P19") (pintype "output"))
    )
    (net (code "46") (name "Net-(U2-TIMEPULSE)") (class "Default")
      (node (ref "R12") (pin "1") (pinfunction "1_1") (pintype "passive"))
      (node (ref "U2") (pin "P53") (pinfunction "TIMEPULSE_P53") (pintype "output"))
    )
    (net (code "47") (name "PPS") (class "Default")
      (node (ref "D5") (pin "A") (pinfunction "A_A") (pintype "passive"))
      (node (ref "J6") (pin "1") (pinfunction "1_1") (pintype "passive"))
      (node (ref "R12") (pin "2") (pinfunction "2_2") (pintype "passive"))
    )
    (net (code "48") (name "RF_IN") (class "Default")
      (node (ref "FB1") (pin "P1") (pinfunction "1_P1") (pintype "passive"))
      (node (ref "J1") (pin "FEED") (pinfunction "SIGNAL_FEED") (pintype "bidirectional"))
      (node (ref "U2") (pin "P2") (pinfunction "RF_IN_P2") (pintype "input"))
    )
    (net (code "49") (name "RTK_STAT") (class "Default")
      (node (ref "D6") (pin "A") (pinfunction "A_A") (pintype "passive"))
      (node (ref "R11") (pin "P8") (pinfunction "2_P8") (pintype "passive"))
    )
    (net (code "50") (name "RXI2") (class "Default")
      (node (ref "J7") (pin "4") (pinfunction "4_4") (pintype "passive"))
      (node (ref "R10") (pin "P7") (pinfunction "2_P7") (pintype "passive"))
    )
    (net (code "51") (name "RXI{slash}MOSI") (class "Default")
      (node (ref "J5") (pin "5") (pinfunction "5_5") (pintype "passive"))
      (node (ref "R9") (pin "P2") (pinfunction "1_P2") (pintype "passive"))
    )
    (net (code "52") (name "SCL{slash}CLK") (class "Default")
      (node (ref "J3") (pin "4") (pinfunction "4_4") (pintype "passive"))
      (node (ref "J4") (pin "4") (pinfunction "4_4") (pintype "passive"))
      (node (ref "J5") (pin "7") (pinfunction "7_7") (pintype "passive"))
      (node (ref "J6") (pin "6") (pinfunction "6_6") (pintype "passive"))
      (node (ref "R16") (pin "1") (pinfunction "1_1") (pintype "passive"))
      (node (ref "R9") (pin "P4") (pinfunction "1_P4") (pintype "passive"))
    )
    (net (code "53") (name "SDA{slash}~{CS}") (class "Default")
      (node (ref "J3") (pin "3") (pinfunction "3_3") (pintype "passive"))
      (node (ref "J4") (pin "3") (pinfunction "3_3") (pintype "passive"))
      (node (ref "J5") (pin "4") (pinfunction "4_4") (pintype "passive"))
      (node (ref "J6") (pin "7") (pinfunction "7_7") (pintype "passive"))
      (node (ref "R23") (pin "1") (pinfunction "1_1") (pintype "passive"))
      (node (ref "R9") (pin "P3") (pinfunction "1_P3") (pintype "passive"))
    )
    (net (code "54") (name "SHIELD") (class "Default")
      (node (ref "J2") (pin "SHLD1") (pinfunction "SHLD_SHLD1") (pintype "bidirectional"))
      (node (ref "J2") (pin "SHLD2") (pinfunction "SHLD_SHLD2") (pintype "bidirectional"))
      (node (ref "J2") (pin "SHLD3") (pinfunction "SHLD_SHLD3") (pintype "bidirectional"))
      (node (ref "J2") (pin "SHLD4") (pinfunction "SHLD_SHLD4") (pintype "bidirectional"))
    )
    (net (code "55") (name "TXO2") (class "Default")
      (node (ref "J7") (pin "5") (pinfunction "5_5") (pintype "passive"))
      (node (ref "R10") (pin "P8") (pinfunction "2_P8") (pintype "passive"))
    )
    (net (code "56") (name "TXO{slash}MISO") (class "Default")
      (node (ref "J5") (pin "6") (pinfunction "6_6") (pintype "passive"))
      (node (ref "R9") (pin "P1") (pinfunction "1_P1") (pintype "passive"))
    )
    (net (code "57") (name "TX_READY") (class "Default")
      (node (ref "J6") (pin "5") (pinfunction "5_5") (pintype "passive"))
      (node (ref "R8") (pin "P1") (pinfunction "1_P1") (pintype "passive"))
    )
    (net (code "58") (name "VIN") (class "Default")
      (node (ref "C9") (pin "1") (pinfunction "1_1") (pintype "passive"))
      (node (ref "D3") (pin "5") (pinfunction "5_5") (pintype "bidirectional"))
      (node (ref "J2") (pin "VBUS1") (pinfunction "VBUS_VBUS1") (pintype "bidirectional"))
      (node (ref "J2") (pin "VBUS2") (pinfunction "VBUS_VBUS2") (pintype "bidirectional"))
      (node (ref "J5") (pin "2") (pinfunction "2_2") (pintype "passive"))
      (node (ref "U5") (pin "1") (pinfunction "IN_1") (pintype "input"))
      (node (ref "U5") (pin "3") (pinfunction "EN_3") (pintype "input"))
    )
    (net (code "59") (name "V_BATT") (class "Default")
      (node (ref "BT1") (pin "+") (pinfunction "+_+") (pintype "power_in"))
      (node (ref "R24") (pin "1") (pinfunction "1_1") (pintype "passive"))
      (node (ref "U2") (pin "P36") (pinfunction "V_BKCP_P36") (pintype "power_in"))
    )
    (net (code "60") (name "V_RF") (class "Default")
      (node (ref "R13") (pin "2") (pinfunction "2_2") (pintype "passive"))
      (node (ref "U2") (pin "P7") (pinfunction "V_RF_P7") (pintype "output"))
    )
    (net (code "61") (name "WT+") (class "Default")
      (node (ref "J5") (pin "11") (pinfunction "11_11") (pintype "passive"))
      (node (ref "R2") (pin "1") (pinfunction "1_1") (pintype "passive"))
    )
    (net (code "62") (name "WT_IN") (class "Default")
      (node (ref "R6") (pin "2") (pinfunction "2_2") (pintype "passive"))
      (node (ref "U1") (pin "P1") (pinfunction "ANODE1_P1") (pintype "input"))
    )
    (net (code "63") (name "WT_OUT") (class "Default")
      (node (ref "R10") (pin "P5") (pinfunction "2_P5") (pintype "passive"))
      (node (ref "U3") (pin "P4") (pinfunction "Y_P4") (pintype "bidirectional"))
    )
    (net (code "64") (name "WT_SCHMITT") (class "Default")
      (node (ref "R7") (pin "1") (pinfunction "1_1") (pintype "passive"))
      (node (ref "U1") (pin "P7") (pinfunction "VOUT1_P7") (pintype "output"))
      (node (ref "U3") (pin "P2") (pinfunction "A_P2") (pintype "bidirectional"))
    )
    (net (code "65") (name "unconnected-(J7-Pad2)") (class "Default")
      (node (ref "J7") (pin "2") (pinfunction "2_2") (pintype "passive"))
    )
    (net (code "66") (name "unconnected-(J7-Pad3)") (class "Default")
      (node (ref "J7") (pin "3") (pinfunction "3_3") (pintype "passive"))
    )
    (net (code "67") (name "unconnected-(J7-Pad6)") (class "Default")
      (node (ref "J7") (pin "6") (pinfunction "6_6") (pintype "passive"))
    )
    (net (code "68") (name "unconnected-(U2-ANT_DETECT-PadP4)") (class "Default")
      (node (ref "U2") (pin "P4") (pinfunction "ANT_DETECT_P4") (pintype "input"))
    )
    (net (code "69") (name "unconnected-(U2-ANT_OFF-PadP5)") (class "Default")
      (node (ref "U2") (pin "P5") (pinfunction "ANT_OFF_P5") (pintype "output"))
    )
    (net (code "70") (name "unconnected-(U2-RSVD-PadP8)") (class "Default")
      (node (ref "U2") (pin "P8") (pinfunction "RSVD_P8") (pintype "no_connect"))
    )
    (net (code "71") (name "unconnected-(U2-RSVD-PadP9)") (class "Default")
      (node (ref "U2") (pin "P9") (pinfunction "RSVD_P9") (pintype "no_connect"))
    )
    (net (code "72") (name "unconnected-(U2-RSVD-PadP10)") (class "Default")
      (node (ref "U2") (pin "P10") (pinfunction "RSVD_P10") (pintype "no_connect"))
    )
    (net (code "73") (name "unconnected-(U2-RSVD-PadP11)") (class "Default")
      (node (ref "U2") (pin "P11") (pinfunction "RSVD_P11") (pintype "no_connect"))
    )
    (net (code "74") (name "unconnected-(U2-RSVD-PadP13)") (class "Default")
      (node (ref "U2") (pin "P13") (pinfunction "RSVD_P13") (pintype "no_connect"))
    )
    (net (code "75") (name "unconnected-(U2-RSVD-PadP15)") (class "Default")
      (node (ref "U2") (pin "P15") (pinfunction "RSVD_P15") (pintype "no_connect"))
    )
    (net (code "76") (name "unconnected-(U2-RSVD-PadP16)") (class "Default")
      (node (ref "U2") (pin "P16") (pinfunction "RSVD_P16") (pintype "no_connect"))
    )
    (net (code "77") (name "unconnected-(U2-RSVD-PadP17)") (class "Default")
      (node (ref "U2") (pin "P17") (pinfunction "RSVD_P17") (pintype "no_connect"))
    )
    (net (code "78") (name "unconnected-(U2-RSVD-PadP18)") (class "Default")
      (node (ref "U2") (pin "P18") (pinfunction "RSVD_P18") (pintype "no_connect"))
    )
    (net (code "79") (name "unconnected-(U2-RSVD-PadP21)") (class "Default")
      (node (ref "U2") (pin "P21") (pinfunction "RSVD_P21") (pintype "no_connect"))
    )
    (net (code "80") (name "unconnected-(U2-RSVD-PadP24)") (class "Default")
      (node (ref "U2") (pin "P24") (pinfunction "RSVD_P24") (pintype "no_connect"))
    )
    (net (code "81") (name "unconnected-(U2-RSVD-PadP25)") (class "Default")
      (node (ref "U2") (pin "P25") (pinfunction "RSVD_P25") (pintype "no_connect"))
    )
    (net (code "82") (name "unconnected-(U2-RSVD-PadP28)") (class "Default")
      (node (ref "U2") (pin "P28") (pinfunction "RSVD_P28") (pintype "no_connect"))
    )
    (net (code "83") (name "unconnected-(U2-RSVD-PadP29)") (class "Default")
      (node (ref "U2") (pin "P29") (pinfunction "RSVD_P29") (pintype "no_connect"))
    )
    (net (code "84") (name "unconnected-(U2-RSVD-PadP30)") (class "Default")
      (node (ref "U2") (pin "P30") (pinfunction "RSVD_P30") (pintype "no_connect"))
    )
    (net (code "85") (name "unconnected-(U2-RSVD-PadP31)") (class "Default")
      (node (ref "U2") (pin "P31") (pinfunction "RSVD_P31") (pintype "no_connect"))
    )
    (net (code "86") (name "unconnected-(U2-RSVD-PadP35)") (class "Default")
      (node (ref "U2") (pin "P35") (pinfunction "RSVD_P35") (pintype "no_connect"))
    )
    (net (code "87") (name "unconnected-(U2-RSVD-PadP52)") (class "Default")
      (node (ref "U2") (pin "P52") (pinfunction "RSVD_P52") (pintype "no_connect"))
    )
    (net (code "88") (name "unconnected-(U2-RSVD-PadP54)") (class "Default")
      (node (ref "U2") (pin "P54") (pinfunction "RSVD_P54") (pintype "no_connect"))
    )
    (net (code "89") (name "unconnected-(U2-~{ANT_SHORT}-PadP6)") (class "Default")
      (node (ref "U2") (pin "P6") (pinfunction "~{ANT_SHORT}_P6") (pintype "output"))
    )
    (net (code "90") (name "unconnected-(U3-NC-PadP1)") (class "Default")
      (node (ref "U3") (pin "P1") (pinfunction "NC_P1") (pintype "no_connect"))
    )
    (net (code "91") (name "unconnected-(U3-NC-PadP5)") (class "Default")
      (node (ref "U3") (pin "P5") (pinfunction "NC_P5") (pintype "no_connect"))
    )
    (net (code "92") (name "unconnected-(U4-NC-PadP1)") (class "Default")
      (node (ref "U4") (pin "P1") (pinfunction "NC_P1") (pintype "no_connect"))
    )
    (net (code "93") (name "unconnected-(U4-NC-PadP5)") (class "Default")
      (node (ref "U4") (pin "P5") (pinfunction "NC_P5") (pintype "no_connect"))
    )
    (net (code "94") (name "unconnected-(U5-NC-Pad4)") (class "Default")
      (node (ref "U5") (pin "4") (pinfunction "NC_4") (pintype "no_connect"))
    )
    (net (code "95") (name "~{RESET}") (class "Default")
      (node (ref "J6") (pin "4") (pinfunction "4_4") (pintype "passive"))
      (node (ref "R8") (pin "P2") (pinfunction "1_P2") (pintype "passive"))
    )
    (net (code "96") (name "~{SAFEBOOT}") (class "Default")
      (node (ref "J6") (pin "3") (pinfunction "3_3") (pintype "passive"))
      (node (ref "R8") (pin "P3") (pinfunction "1_P3") (pintype "passive"))
    )
  )
)
